# WIFI.net
KiCad netlist of a schematic drawn in Altium Designer
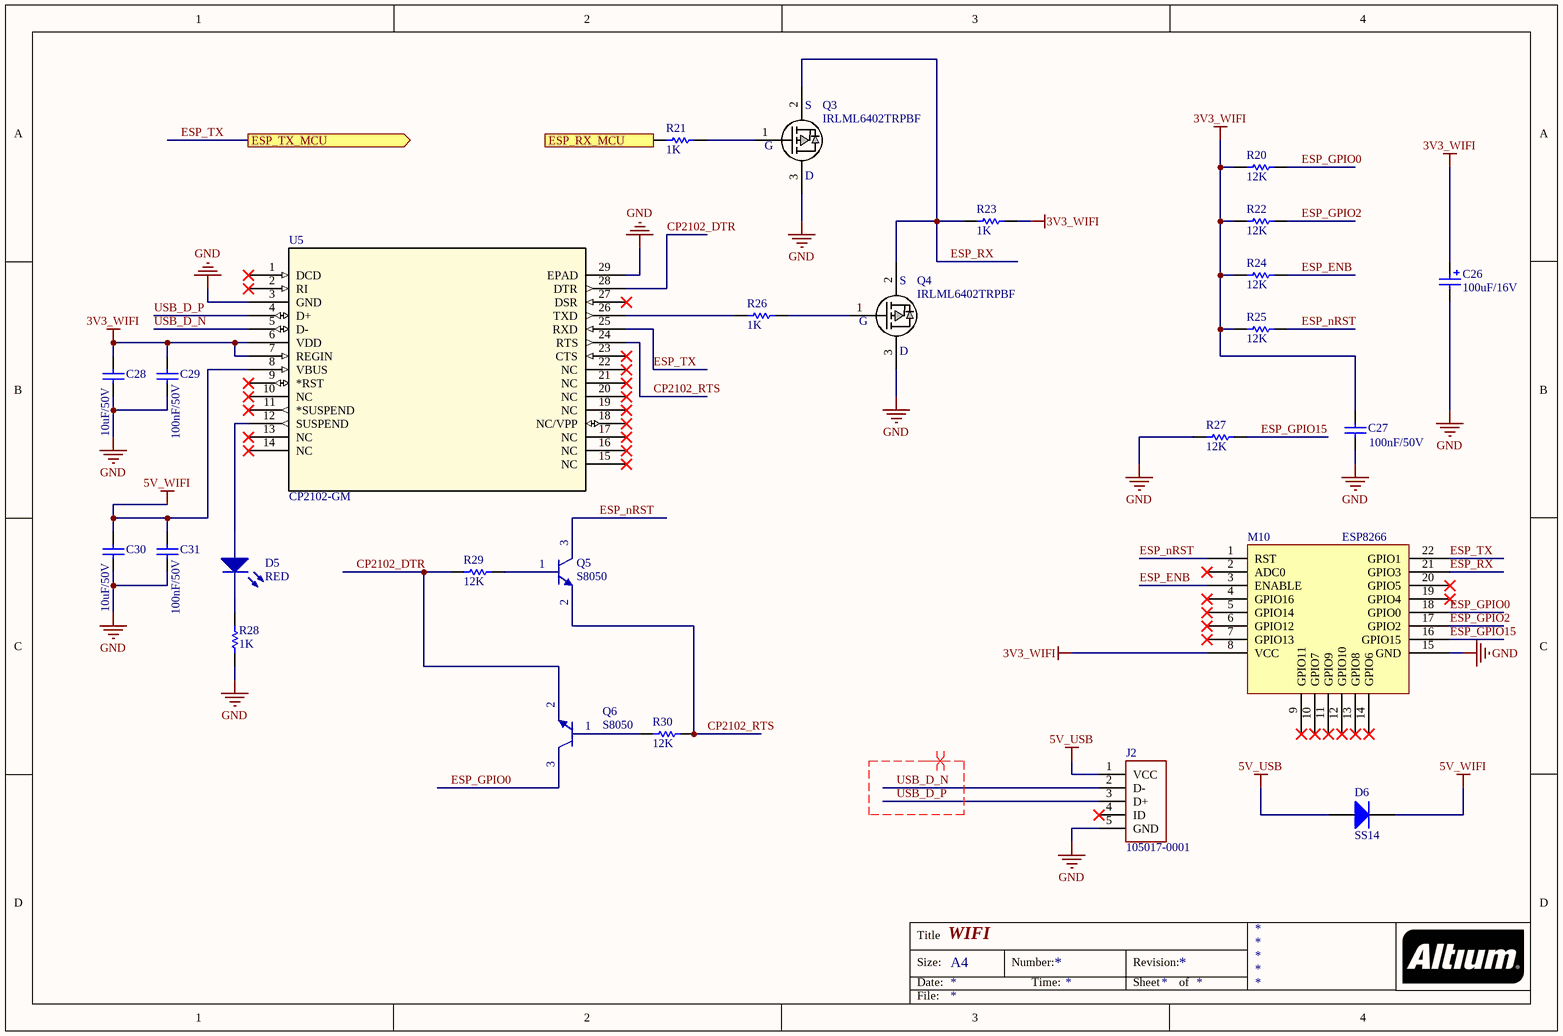
[diagram p0: WIFI.SchDoc]

(export (version "E")
  (design (tool "Eeschema 10.0.6"))
  (components
    (comp (ref "C26")
      (value "100uF/16V")
      (footprint "CAP_SM_TAN")
      (fields
        (field (name "MANUFACTURER") "Nichicon")
        (field (name "MANUFACTURER PART NUMBER") "UWX1C101MCL1GB")
        (field (name "Comment") "TAJB107M006RNJ")
      )
      (libsource (lib "PIF_ROBOT") (part "Cap-Tan-100uF-16V"))
    )
    (comp (ref "C27")
      (value "100nF/50V")
      (footprint "CAP-SM-0805")
      (description "CAP CER 10UF 50V X5R 0805")
      (fields
        (field (name "MANUFACTURER") "Yageo")
        (field (name "MANUFACTURER PART NUMBER") "CC0805KKX5R9BB106")
      )
      (libsource (lib "PIF_ROBOT") (part "Cap-10uF-50V-0805"))
    )
    (comp (ref "C28")
      (value "10uF/50V")
      (footprint "CAP-SM-0805")
      (description "CAP CER 10UF 50V X5R 0805")
      (fields
        (field (name "MANUFACTURER") "Yageo")
        (field (name "MANUFACTURER PART NUMBER") "CC0805KKX5R9BB106")
      )
      (libsource (lib "PIF_ROBOT") (part "Cap-10uF-50V-0805"))
    )
    (comp (ref "C29")
      (value "100nF/50V")
      (footprint "CAP-SM-0805")
      (description "CAP CER 10UF 50V X5R 0805")
      (fields
        (field (name "MANUFACTURER") "Yageo")
        (field (name "MANUFACTURER PART NUMBER") "CC0805KKX5R9BB106")
      )
      (libsource (lib "PIF_ROBOT") (part "Cap-10uF-50V-0805"))
    )
    (comp (ref "C30")
      (value "10uF/50V")
      (footprint "CAP-SM-0805")
      (description "CAP CER 10UF 50V X5R 0805")
      (fields
        (field (name "MANUFACTURER") "Yageo")
        (field (name "MANUFACTURER PART NUMBER") "CC0805KKX5R9BB106")
      )
      (libsource (lib "PIF_ROBOT") (part "Cap-10uF-50V-0805"))
    )
    (comp (ref "C31")
      (value "100nF/50V")
      (footprint "CAP-SM-0805")
      (description "CAP CER 10UF 50V X5R 0805")
      (fields
        (field (name "MANUFACTURER") "Yageo")
        (field (name "MANUFACTURER PART NUMBER") "CC0805KKX5R9BB106")
      )
      (libsource (lib "PIF_ROBOT") (part "Cap-10uF-50V-0805"))
    )
    (comp (ref "D5") (value "RED") (footprint "LED_0805_Blue") (libsource (lib "PIF_C16_lib") (part "LED")))
    (comp (ref "D6")
      (value "SS14")
      (footprint "SS14")
      (description "DIODE SCHOTTKY 40V 1A SMA")
      (fields (field (name "MANUFACTURER") "ON Semiconductor"))
      (libsource (lib "PIF_ROBOT") (part "Diode-SS14"))
    )
    (comp (ref "J2")
      (value "105017-0001")
      (footprint "CONN_105017-0001")
      (description "No Description Available")
      (fields (field (name "COPYRIGHT") "Copyright (C) 2018 Accelerated Designs. All rights reserved"))
      (libsource (lib "PIF_ROBOT") (part "105017-0001"))
    )
    (comp (ref "M10") (value "ESP8266") (footprint "ESP88") (libsource (lib "PIF_ROBOT") (part "ESP8266")))
    (comp (ref "Q3")
      (value "IRLML6402TRPBF")
      (footprint "SOT23_NEX")
      (description "P-Channel 20V 3.7A (Ta) 1.3W (Ta) Surface Mount Micro3™/SOT-23")
      (libsource (lib "PIF_ROBOT") (part "IRLML6402TRPBF"))
    )
    (comp (ref "Q4")
      (value "IRLML6402TRPBF")
      (footprint "SOT23_NEX")
      (description "P-Channel 20V 3.7A (Ta) 1.3W (Ta) Surface Mount Micro3™/SOT-23")
      (libsource (lib "PIF_ROBOT") (part "IRLML6402TRPBF"))
    )
    (comp (ref "Q5") (value "S8050") (footprint "SOT23_NEX") (libsource (lib "PIF_ROBOT") (part "S8050")))
    (comp (ref "Q6") (value "S8050") (footprint "SOT23_NEX") (libsource (lib "PIF_ROBOT") (part "S8050")))
    (comp (ref "R20")
      (value "12K")
      (footprint "RES-SM-0805")
      (description "RES 0 OHM JUMPER 0805")
      (fields
        (field (name "MANUFACTURER") "Vishay Dale")
        (field (name "MANUFACTURER PART NUMBER") "WSL080500000ZEA9")
      )
      (libsource (lib "PIF_ROBOT") (part "Res-0-0805"))
    )
    (comp (ref "R21")
      (value "1K")
      (footprint "RES-SM-0805")
      (description "RES 0 OHM JUMPER 0805")
      (fields
        (field (name "MANUFACTURER") "Vishay Dale")
        (field (name "MANUFACTURER PART NUMBER") "WSL080500000ZEA9")
      )
      (libsource (lib "PIF_ROBOT") (part "Res-0-0805"))
    )
    (comp (ref "R22")
      (value "12K")
      (footprint "RES-SM-0805")
      (description "RES 0 OHM JUMPER 0805")
      (fields
        (field (name "MANUFACTURER") "Vishay Dale")
        (field (name "MANUFACTURER PART NUMBER") "WSL080500000ZEA9")
      )
      (libsource (lib "PIF_ROBOT") (part "Res-0-0805"))
    )
    (comp (ref "R23")
      (value "1K")
      (footprint "RES-SM-0805")
      (description "RES 0 OHM JUMPER 0805")
      (fields
        (field (name "MANUFACTURER") "Vishay Dale")
        (field (name "MANUFACTURER PART NUMBER") "WSL080500000ZEA9")
      )
      (libsource (lib "PIF_ROBOT") (part "Res-0-0805"))
    )
    (comp (ref "R24")
      (value "12K")
      (footprint "RES-SM-0805")
      (description "RES 0 OHM JUMPER 0805")
      (fields
        (field (name "MANUFACTURER") "Vishay Dale")
        (field (name "MANUFACTURER PART NUMBER") "WSL080500000ZEA9")
      )
      (libsource (lib "PIF_ROBOT") (part "Res-0-0805"))
    )
    (comp (ref "R25")
      (value "12K")
      (footprint "RES-SM-0805")
      (description "RES 0 OHM JUMPER 0805")
      (fields
        (field (name "MANUFACTURER") "Vishay Dale")
        (field (name "MANUFACTURER PART NUMBER") "WSL080500000ZEA9")
      )
      (libsource (lib "PIF_ROBOT") (part "Res-0-0805"))
    )
    (comp (ref "R26")
      (value "1K")
      (footprint "RES-SM-0805")
      (description "RES 0 OHM JUMPER 0805")
      (fields
        (field (name "MANUFACTURER") "Vishay Dale")
        (field (name "MANUFACTURER PART NUMBER") "WSL080500000ZEA9")
      )
      (libsource (lib "PIF_ROBOT") (part "Res-0-0805"))
    )
    (comp (ref "R27")
      (value "12K")
      (footprint "RES-SM-0805")
      (description "RES 0 OHM JUMPER 0805")
      (fields
        (field (name "MANUFACTURER") "Vishay Dale")
        (field (name "MANUFACTURER PART NUMBER") "WSL080500000ZEA9")
      )
      (libsource (lib "PIF_ROBOT") (part "Res-0-0805"))
    )
    (comp (ref "R28")
      (value "1K")
      (footprint "RES-SM-0805")
      (description "RES 0 OHM JUMPER 0805")
      (fields
        (field (name "MANUFACTURER") "Vishay Dale")
        (field (name "MANUFACTURER PART NUMBER") "WSL080500000ZEA9")
      )
      (libsource (lib "PIF_ROBOT") (part "Res-0-0805"))
    )
    (comp (ref "R29")
      (value "12K")
      (footprint "RES-SM-0805")
      (description "RES 0 OHM JUMPER 0805")
      (fields
        (field (name "MANUFACTURER") "Vishay Dale")
        (field (name "MANUFACTURER PART NUMBER") "WSL080500000ZEA9")
      )
      (libsource (lib "PIF_ROBOT") (part "Res-0-0805"))
    )
    (comp (ref "R30")
      (value "12K")
      (footprint "RES-SM-0805")
      (description "RES 0 OHM JUMPER 0805")
      (fields
        (field (name "MANUFACTURER") "Vishay Dale")
        (field (name "MANUFACTURER PART NUMBER") "WSL080500000ZEA9")
      )
      (libsource (lib "PIF_ROBOT") (part "Res-0-0805"))
    )
    (comp (ref "U5")
      (value "CP2102-GM")
      (footprint "CP2102")
      (description "No Description Available")
      (fields (field (name "COPYRIGHT") "Copyright (C) 2018 Accelerated Designs. All rights reserved"))
      (libsource (lib "PIF_ROBOT") (part "CP2102-GM"))
    )
  )
  (nets
    (net (code "1") (name "/CP2102_DTR") (class "Default")
      (node (ref "Q6") (pin "2") (pinfunction "E_2") (pintype "passive"))
      (node (ref "R29") (pin "1") (pinfunction "1_1") (pintype "passive"))
      (node (ref "U5") (pin "28") (pinfunction "DTR_28") (pintype "output"))
    )
    (net (code "2") (name "/CP2102_RTS") (class "Default")
      (node (ref "Q5") (pin "2") (pinfunction "E_2") (pintype "passive"))
      (node (ref "R30") (pin "2") (pinfunction "2_2") (pintype "passive"))
      (node (ref "U5") (pin "24") (pinfunction "RTS_24") (pintype "output"))
    )
    (net (code "3") (name "/ESP_ENB") (class "Default")
      (node (ref "M10") (pin "3") (pinfunction "ENABLE_3") (pintype "passive"))
      (node (ref "R24") (pin "2") (pinfunction "2_2") (pintype "passive"))
    )
    (net (code "4") (name "/ESP_GPIO0") (class "Default")
      (node (ref "M10") (pin "18") (pinfunction "GPIO0_18") (pintype "passive"))
      (node (ref "Q6") (pin "3") (pinfunction "C_3") (pintype "passive"))
      (node (ref "R20") (pin "2") (pinfunction "2_2") (pintype "passive"))
    )
    (net (code "5") (name "/ESP_GPIO2") (class "Default")
      (node (ref "M10") (pin "17") (pinfunction "GPIO2_17") (pintype "passive"))
      (node (ref "R22") (pin "2") (pinfunction "2_2") (pintype "passive"))
    )
    (net (code "6") (name "/ESP_GPIO15") (class "Default")
      (node (ref "M10") (pin "16") (pinfunction "GPIO15_16") (pintype "passive"))
      (node (ref "R27") (pin "2") (pinfunction "2_2") (pintype "passive"))
    )
    (net (code "7") (name "/ESP_RX") (class "Default")
      (node (ref "M10") (pin "21") (pinfunction "GPIO3_21") (pintype "passive"))
      (node (ref "Q3") (pin "2") (pinfunction "S_2") (pintype "passive"))
      (node (ref "Q4") (pin "2") (pinfunction "S_2") (pintype "passive"))
      (node (ref "R23") (pin "2") (pinfunction "2_2") (pintype "passive"))
    )
    (net (code "8") (name "/ESP_RX_MCU") (class "Default")
      (node (ref "R21") (pin "1") (pinfunction "1_1") (pintype "passive"))
    )
    (net (code "9") (name "/ESP_TX") (class "Default")
      (node (ref "M10") (pin "22") (pinfunction "GPIO1_22") (pintype "passive"))
      (node (ref "U5") (pin "25") (pinfunction "RXD_25") (pintype "input"))
    )
    (net (code "10") (name "/ESP_nRST") (class "Default")
      (node (ref "M10") (pin "1") (pinfunction "RST_1") (pintype "passive"))
      (node (ref "Q5") (pin "3") (pinfunction "C_3") (pintype "passive"))
      (node (ref "R25") (pin "2") (pinfunction "2_2") (pintype "passive"))
    )
    (net (code "11") (name "/USB_D_N") (class "Default")
      (node (ref "J2") (pin "2") (pinfunction "D-_2") (pintype "passive"))
      (node (ref "U5") (pin "5") (pinfunction "D-_5") (pintype "bidirectional"))
    )
    (net (code "12") (name "/USB_D_P") (class "Default")
      (node (ref "J2") (pin "3") (pinfunction "D+_3") (pintype "passive"))
      (node (ref "U5") (pin "4") (pinfunction "D+_4") (pintype "bidirectional"))
    )
    (net (code "13") (name "3V3_WIFI") (class "Default")
      (node (ref "C26") (pin "1") (pinfunction "1_1") (pintype "passive"))
      (node (ref "C27") (pin "1") (pinfunction "1_1") (pintype "passive"))
      (node (ref "C28") (pin "1") (pinfunction "1_1") (pintype "passive"))
      (node (ref "C29") (pin "1") (pinfunction "1_1") (pintype "passive"))
      (node (ref "M10") (pin "8") (pinfunction "VCC_8") (pintype "passive"))
      (node (ref "R20") (pin "1") (pinfunction "1_1") (pintype "passive"))
      (node (ref "R22") (pin "1") (pinfunction "1_1") (pintype "passive"))
      (node (ref "R23") (pin "1") (pinfunction "1_1") (pintype "passive"))
      (node (ref "R24") (pin "1") (pinfunction "1_1") (pintype "passive"))
      (node (ref "R25") (pin "1") (pinfunction "1_1") (pintype "passive"))
      (node (ref "U5") (pin "6") (pinfunction "VDD_6") (pintype "power_in"))
      (node (ref "U5") (pin "7") (pinfunction "REGIN_7") (pintype "input"))
    )
    (net (code "14") (name "5V_USB") (class "Default")
      (node (ref "D6") (pin "2") (pinfunction "A_2") (pintype "passive"))
      (node (ref "J2") (pin "1") (pinfunction "VCC_1") (pintype "passive"))
    )
    (net (code "15") (name "5V_WIFI") (class "Default")
      (node (ref "C30") (pin "1") (pinfunction "1_1") (pintype "passive"))
      (node (ref "C31") (pin "1") (pinfunction "1_1") (pintype "passive"))
      (node (ref "D6") (pin "1") (pinfunction "K_1") (pintype "passive"))
      (node (ref "U5") (pin "8") (pinfunction "VBUS_8") (pintype "input"))
    )
    (net (code "16") (name "GND") (class "Default")
      (node (ref "C26") (pin "2") (pinfunction "2_2") (pintype "passive"))
      (node (ref "C27") (pin "2") (pinfunction "2_2") (pintype "passive"))
      (node (ref "C28") (pin "2") (pinfunction "2_2") (pintype "passive"))
      (node (ref "C29") (pin "2") (pinfunction "2_2") (pintype "passive"))
      (node (ref "C30") (pin "2") (pinfunction "2_2") (pintype "passive"))
      (node (ref "C31") (pin "2") (pinfunction "2_2") (pintype "passive"))
      (node (ref "J2") (pin "5") (pinfunction "GND_5") (pintype "passive"))
      (node (ref "M10") (pin "15") (pinfunction "GND_15") (pintype "passive"))
      (node (ref "Q3") (pin "3") (pinfunction "D_3") (pintype "passive"))
      (node (ref "Q4") (pin "3") (pinfunction "D_3") (pintype "passive"))
      (node (ref "R27") (pin "1") (pinfunction "1_1") (pintype "passive"))
      (node (ref "R28") (pin "1") (pinfunction "1_1") (pintype "passive"))
      (node (ref "U5") (pin "29") (pinfunction "EPAD_29") (pintype "passive"))
      (node (ref "U5") (pin "3") (pinfunction "GND_3") (pintype "power_in"))
    )
    (net (code "17") (name "Net-(D5-A)") (class "Default")
      (node (ref "D5") (pin "1") (pinfunction "A_1") (pintype "passive"))
      (node (ref "U5") (pin "12") (pinfunction "SUSPEND_12") (pintype "output"))
    )
    (net (code "18") (name "Net-(D5-K)") (class "Default")
      (node (ref "D5") (pin "2") (pinfunction "K_2") (pintype "passive"))
      (node (ref "R28") (pin "2") (pinfunction "2_2") (pintype "passive"))
    )
    (net (code "19") (name "Net-(Q3-G)") (class "Default")
      (node (ref "Q3") (pin "1") (pinfunction "G_1") (pintype "passive"))
      (node (ref "R21") (pin "2") (pinfunction "2_2") (pintype "passive"))
    )
    (net (code "20") (name "Net-(Q4-G)") (class "Default")
      (node (ref "Q4") (pin "1") (pinfunction "G_1") (pintype "passive"))
      (node (ref "R26") (pin "2") (pinfunction "2_2") (pintype "passive"))
    )
    (net (code "21") (name "Net-(Q5-B)") (class "Default")
      (node (ref "Q5") (pin "1") (pinfunction "B_1") (pintype "passive"))
      (node (ref "R29") (pin "2") (pinfunction "2_2") (pintype "passive"))
    )
    (net (code "22") (name "Net-(Q6-B)") (class "Default")
      (node (ref "Q6") (pin "1") (pinfunction "B_1") (pintype "passive"))
      (node (ref "R30") (pin "1") (pinfunction "1_1") (pintype "passive"))
    )
    (net (code "23") (name "Net-(U5-TXD)") (class "Default")
      (node (ref "R26") (pin "1") (pinfunction "1_1") (pintype "passive"))
      (node (ref "U5") (pin "26") (pinfunction "TXD_26") (pintype "output"))
    )
    (net (code "24") (name "unconnected-(J2-ID-Pad4)") (class "Default")
      (node (ref "J2") (pin "4") (pinfunction "ID_4") (pintype "passive+no_connect"))
    )
    (net (code "25") (name "unconnected-(M10-ADC0-Pad2)") (class "Default")
      (node (ref "M10") (pin "2") (pinfunction "ADC0_2") (pintype "passive+no_connect"))
    )
    (net (code "26") (name "unconnected-(M10-GPIO4-Pad19)") (class "Default")
      (node (ref "M10") (pin "19") (pinfunction "GPIO4_19") (pintype "passive+no_connect"))
    )
    (net (code "27") (name "unconnected-(M10-GPIO5-Pad20)") (class "Default")
      (node (ref "M10") (pin "20") (pinfunction "GPIO5_20") (pintype "passive+no_connect"))
    )
    (net (code "28") (name "unconnected-(M10-GPIO6-Pad14)") (class "Default")
      (node (ref "M10") (pin "14") (pinfunction "GPIO6_14") (pintype "passive+no_connect"))
    )
    (net (code "29") (name "unconnected-(M10-GPIO7-Pad10)") (class "Default")
      (node (ref "M10") (pin "10") (pinfunction "GPIO7_10") (pintype "passive+no_connect"))
    )
    (net (code "30") (name "unconnected-(M10-GPIO8-Pad13)") (class "Default")
      (node (ref "M10") (pin "13") (pinfunction "GPIO8_13") (pintype "passive+no_connect"))
    )
    (net (code "31") (name "unconnected-(M10-GPIO9-Pad11)") (class "Default")
      (node (ref "M10") (pin "11") (pinfunction "GPIO9_11") (pintype "passive+no_connect"))
    )
    (net (code "32") (name "unconnected-(M10-GPIO10-Pad12)") (class "Default")
      (node (ref "M10") (pin "12") (pinfunction "GPIO10_12") (pintype "passive+no_connect"))
    )
    (net (code "33") (name "unconnected-(M10-GPIO11-Pad9)") (class "Default")
      (node (ref "M10") (pin "9") (pinfunction "GPIO11_9") (pintype "passive+no_connect"))
    )
    (net (code "34") (name "unconnected-(M10-GPIO12-Pad6)") (class "Default")
      (node (ref "M10") (pin "6") (pinfunction "GPIO12_6") (pintype "passive+no_connect"))
    )
    (net (code "35") (name "unconnected-(M10-GPIO13-Pad7)") (class "Default")
      (node (ref "M10") (pin "7") (pinfunction "GPIO13_7") (pintype "passive+no_connect"))
    )
    (net (code "36") (name "unconnected-(M10-GPIO14-Pad5)") (class "Default")
      (node (ref "M10") (pin "5") (pinfunction "GPIO14_5") (pintype "passive+no_connect"))
    )
    (net (code "37") (name "unconnected-(M10-GPIO16-Pad4)") (class "Default")
      (node (ref "M10") (pin "4") (pinfunction "GPIO16_4") (pintype "passive+no_connect"))
    )
    (net (code "38") (name "unconnected-(U5-*RST-Pad9)") (class "Default")
      (node (ref "U5") (pin "9") (pinfunction "*RST_9") (pintype "bidirectional+no_connect"))
    )
    (net (code "39") (name "unconnected-(U5-*SUSPEND-Pad11)") (class "Default")
      (node (ref "U5") (pin "11") (pinfunction "*SUSPEND_11") (pintype "output+no_connect"))
    )
    (net (code "40") (name "unconnected-(U5-CTS-Pad23)") (class "Default")
      (node (ref "U5") (pin "23") (pinfunction "CTS_23") (pintype "input+no_connect"))
    )
    (net (code "41") (name "unconnected-(U5-DCD-Pad1)") (class "Default")
      (node (ref "U5") (pin "1") (pinfunction "DCD_1") (pintype "input+no_connect"))
    )
    (net (code "42") (name "unconnected-(U5-DSR-Pad27)") (class "Default")
      (node (ref "U5") (pin "27") (pinfunction "DSR_27") (pintype "input+no_connect"))
    )
    (net (code "43") (name "unconnected-(U5-NC-Pad10)") (class "Default")
      (node (ref "U5") (pin "10") (pinfunction "NC_10") (pintype "passive+no_connect"))
    )
    (net (code "44") (name "unconnected-(U5-NC-Pad13)") (class "Default")
      (node (ref "U5") (pin "13") (pinfunction "NC_13") (pintype "passive+no_connect"))
    )
    (net (code "45") (name "unconnected-(U5-NC-Pad14)") (class "Default")
      (node (ref "U5") (pin "14") (pinfunction "NC_14") (pintype "passive+no_connect"))
    )
    (net (code "46") (name "unconnected-(U5-NC-Pad15)") (class "Default")
      (node (ref "U5") (pin "15") (pinfunction "NC_15") (pintype "passive+no_connect"))
    )
    (net (code "47") (name "unconnected-(U5-NC-Pad16)") (class "Default")
      (node (ref "U5") (pin "16") (pinfunction "NC_16") (pintype "passive+no_connect"))
    )
    (net (code "48") (name "unconnected-(U5-NC-Pad17)") (class "Default")
      (node (ref "U5") (pin "17") (pinfunction "NC_17") (pintype "passive+no_connect"))
    )
    (net (code "49") (name "unconnected-(U5-NC-Pad19)") (class "Default")
      (node (ref "U5") (pin "19") (pinfunction "NC_19") (pintype "passive+no_connect"))
    )
    (net (code "50") (name "unconnected-(U5-NC-Pad20)") (class "Default")
      (node (ref "U5") (pin "20") (pinfunction "NC_20") (pintype "passive+no_connect"))
    )
    (net (code "51") (name "unconnected-(U5-NC-Pad21)") (class "Default")
      (node (ref "U5") (pin "21") (pinfunction "NC_21") (pintype "passive+no_connect"))
    )
    (net (code "52") (name "unconnected-(U5-NC-Pad22)") (class "Default")
      (node (ref "U5") (pin "22") (pinfunction "NC_22") (pintype "passive+no_connect"))
    )
    (net (code "53") (name "unconnected-(U5-NC{slash}VPP-Pad18)") (class "Default")
      (node (ref "U5") (pin "18") (pinfunction "NC/VPP_18") (pintype "bidirectional+no_connect"))
    )
    (net (code "54") (name "unconnected-(U5-RI-Pad2)") (class "Default")
      (node (ref "U5") (pin "2") (pinfunction "RI_2") (pintype "input+no_connect"))
    )
  )
)
